# mini_board0.net
KiCad netlist of a schematic drawn in EAGLE
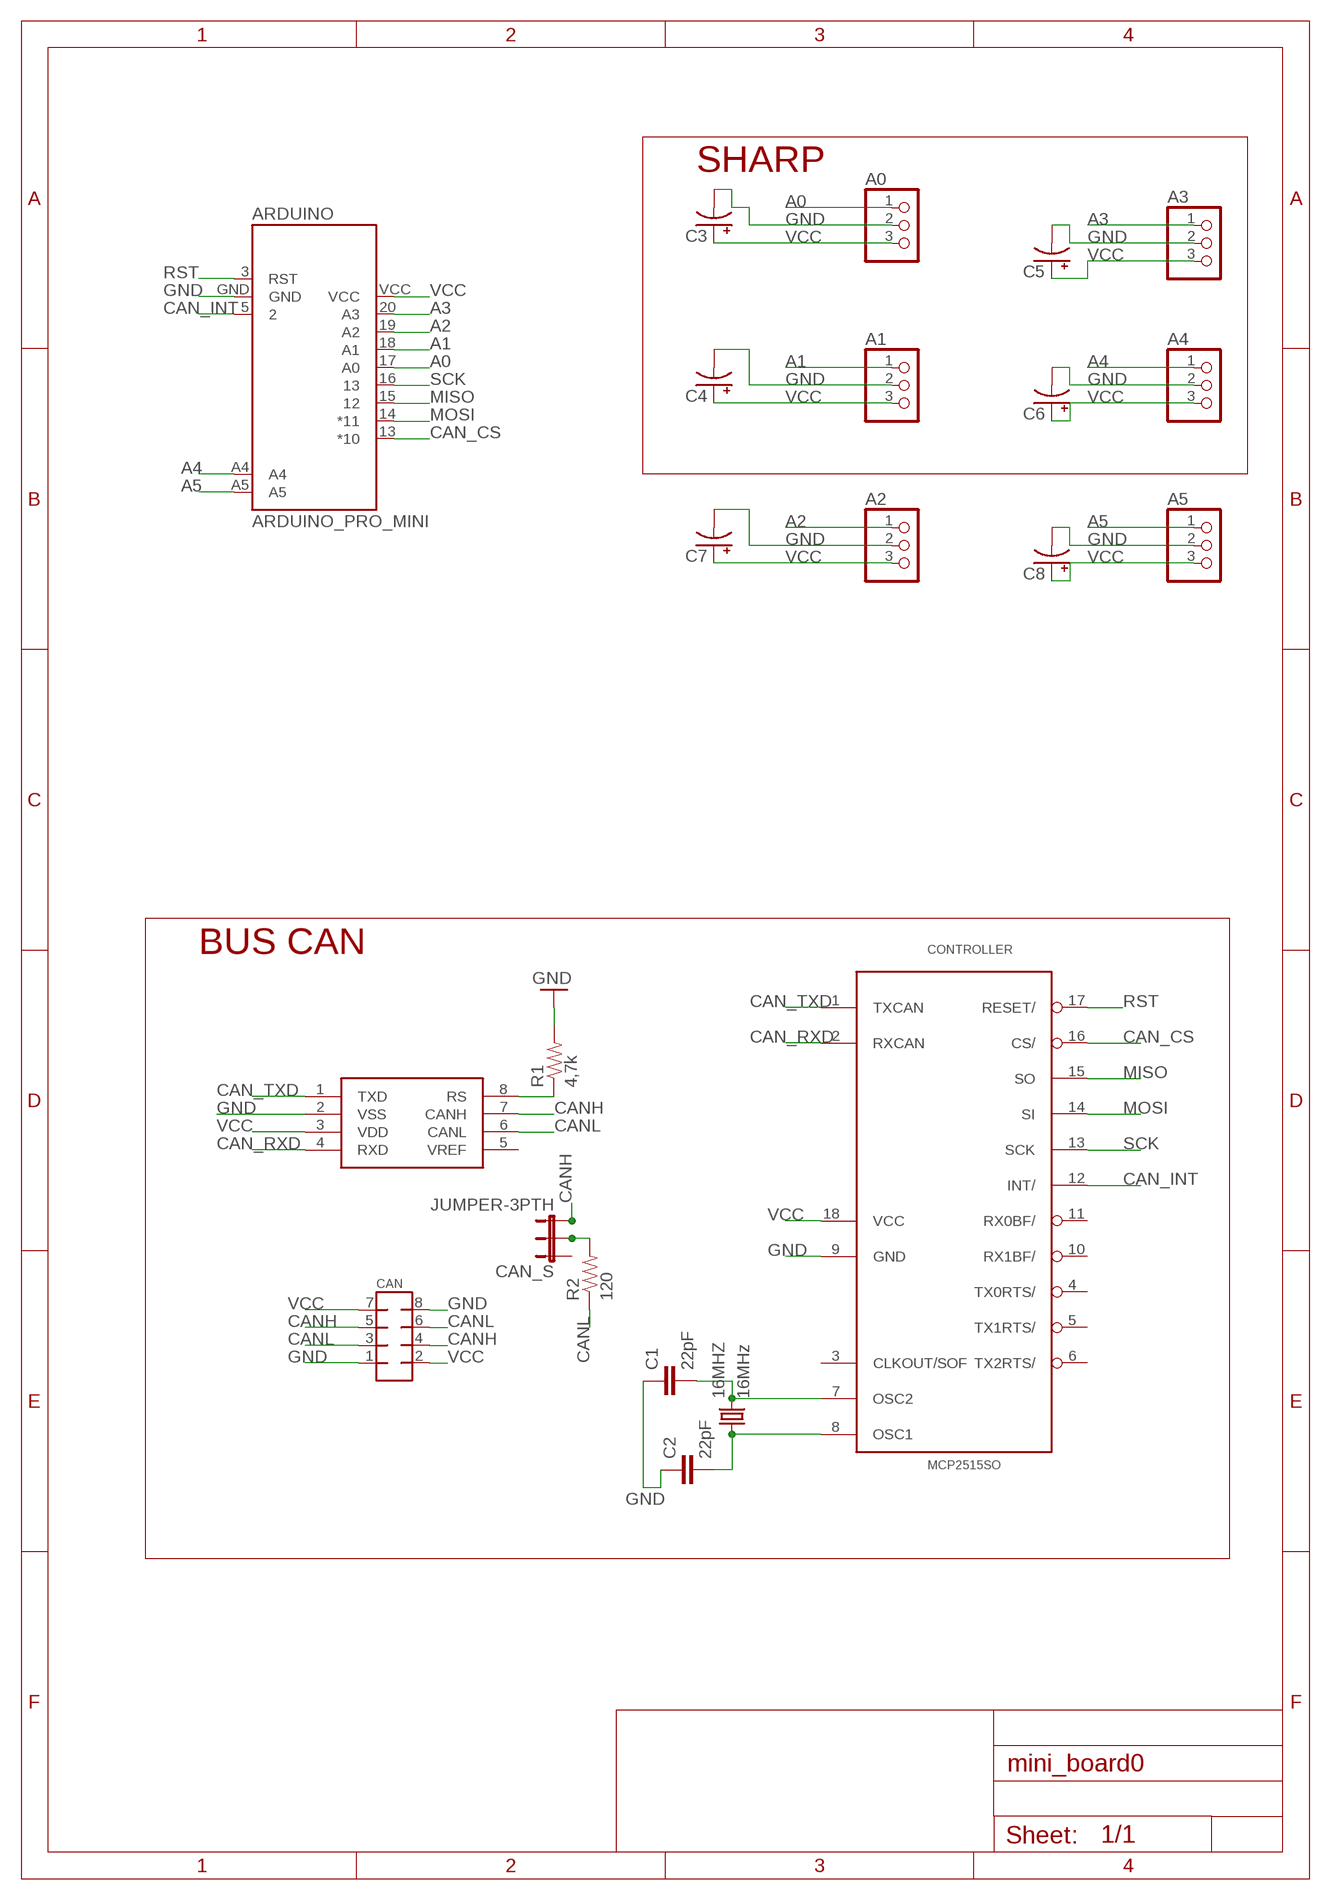
[diagram p0: schematic, sheet 1]

(export (version "E")
  (design (tool "Eeschema 10.0.6"))
  (components
    (comp (ref "16MHZ")
      (value "16MHz")
      (footprint "eagle-import:HC49_S")
      (libsource (lib "eagle-import") (part "CRYSTALHC49S"))
    )
    (comp (ref "A0")
      (value "PINHD-1X3/90")
      (footprint "eagle-import:1X03_90")
      (libsource (lib "eagle-import") (part "PINHD-1X3/90"))
    )
    (comp (ref "A1")
      (value "PINHD-1X3/90")
      (footprint "eagle-import:1X03_90")
      (libsource (lib "eagle-import") (part "PINHD-1X3/90"))
    )
    (comp (ref "A2")
      (value "PINHD-1X3/90")
      (footprint "eagle-import:1X03_90")
      (libsource (lib "eagle-import") (part "PINHD-1X3/90"))
    )
    (comp (ref "A3")
      (value "PINHD-1X3/90")
      (footprint "eagle-import:1X03_90")
      (libsource (lib "eagle-import") (part "PINHD-1X3/90"))
    )
    (comp (ref "A4")
      (value "PINHD-1X3/90")
      (footprint "eagle-import:1X03_90")
      (libsource (lib "eagle-import") (part "PINHD-1X3/90"))
    )
    (comp (ref "A5")
      (value "PINHD-1X3/90")
      (footprint "eagle-import:1X03_90")
      (libsource (lib "eagle-import") (part "PINHD-1X3/90"))
    )
    (comp (ref "ARDUINO")
      (value "ARDUINO_PRO_MINI")
      (footprint "eagle-import:ARDUINO_PRO_MINI")
      (libsource (lib "eagle-import") (part "ARDUINO_PRO_MINI"))
    )
    (comp (ref "C1")
      (value "22pF")
      (footprint "eagle-import:0805")
      (libsource (lib "eagle-import") (part "CAP0805"))
    )
    (comp (ref "C2")
      (value "22pF")
      (footprint "eagle-import:0805")
      (libsource (lib "eagle-import") (part "CAP0805"))
    )
    (comp (ref "C3")
      (value "CAP_POLPTH2")
      (footprint "eagle-import:CPOL-RADIAL-10UF-25V")
      (libsource (lib "eagle-import") (part "CAP_POLPTH2"))
    )
    (comp (ref "C4")
      (value "CAP_POLPTH2")
      (footprint "eagle-import:CPOL-RADIAL-10UF-25V")
      (libsource (lib "eagle-import") (part "CAP_POLPTH2"))
    )
    (comp (ref "C5")
      (value "CAP_POLPTH2")
      (footprint "eagle-import:CPOL-RADIAL-10UF-25V")
      (libsource (lib "eagle-import") (part "CAP_POLPTH2"))
    )
    (comp (ref "C6")
      (value "CAP_POLPTH2")
      (footprint "eagle-import:CPOL-RADIAL-10UF-25V")
      (libsource (lib "eagle-import") (part "CAP_POLPTH2"))
    )
    (comp (ref "C7")
      (value "CAP_POLPTH2")
      (footprint "eagle-import:CPOL-RADIAL-10UF-25V")
      (libsource (lib "eagle-import") (part "CAP_POLPTH2"))
    )
    (comp (ref "C8")
      (value "CAP_POLPTH2")
      (footprint "eagle-import:CPOL-RADIAL-10UF-25V")
      (libsource (lib "eagle-import") (part "CAP_POLPTH2"))
    )
    (comp (ref "CAN")
      (value "MMATCH-8-PTH")
      (footprint "eagle-import:AMP-215079-8")
      (libsource (lib "eagle-import") (part "MMATCH-8-PTH"))
    )
    (comp (ref "CAN_S")
      (value "JUMPER-3PTH")
      (footprint "eagle-import:1X03")
      (libsource (lib "eagle-import") (part "JUMPER-3PTH"))
    )
    (comp (ref "CONTROLLER")
      (value "MCP2515SO")
      (footprint "eagle-import:SO18L")
      (libsource (lib "eagle-import") (part "MCP2515SO"))
    )
    (comp (ref "R1")
      (value "4,7k")
      (footprint "eagle-import:0805")
      (libsource (lib "eagle-import") (part "RESISTOR0805-RES"))
    )
    (comp (ref "R2")
      (value "120")
      (footprint "eagle-import:0805")
      (libsource (lib "eagle-import") (part "RESISTOR0805-RES"))
    )
    (comp (ref "U1")
      (value "MCP2551")
      (footprint "eagle-import:SO08")
      (libsource (lib "eagle-import") (part "MCP2551"))
    )
  )
  (nets
    (net (code "1") (name "/A0") (class "Default")
      (node (ref "A0") (pin "1") (pinfunction "1_1") (pintype "passive"))
      (node (ref "ARDUINO") (pin "17") (pinfunction "A0_17") (pintype "bidirectional"))
    )
    (net (code "2") (name "/A1") (class "Default")
      (node (ref "A1") (pin "1") (pinfunction "1_1") (pintype "passive"))
      (node (ref "ARDUINO") (pin "18") (pinfunction "A1_18") (pintype "bidirectional"))
    )
    (net (code "3") (name "/A2") (class "Default")
      (node (ref "A2") (pin "1") (pinfunction "1_1") (pintype "passive"))
      (node (ref "ARDUINO") (pin "19") (pinfunction "A2_19") (pintype "bidirectional"))
    )
    (net (code "4") (name "/A3") (class "Default")
      (node (ref "A3") (pin "1") (pinfunction "1_1") (pintype "passive"))
      (node (ref "ARDUINO") (pin "20") (pinfunction "A3_20") (pintype "bidirectional"))
    )
    (net (code "5") (name "/A4") (class "Default")
      (node (ref "A4") (pin "1") (pinfunction "1_1") (pintype "passive"))
      (node (ref "ARDUINO") (pin "A4") (pinfunction "A4_A4") (pintype "bidirectional"))
    )
    (net (code "6") (name "/A5") (class "Default")
      (node (ref "A5") (pin "1") (pinfunction "1_1") (pintype "passive"))
      (node (ref "ARDUINO") (pin "A5") (pinfunction "A5_A5") (pintype "bidirectional"))
    )
    (net (code "7") (name "/CANH") (class "Default")
      (node (ref "CAN") (pin "4") (pinfunction "4_4") (pintype "bidirectional"))
      (node (ref "CAN") (pin "5") (pinfunction "5_5") (pintype "bidirectional"))
      (node (ref "CAN_S") (pin "3") (pinfunction "3_3") (pintype "passive"))
      (node (ref "U1") (pin "7") (pinfunction "CANH_7") (pintype "bidirectional"))
    )
    (net (code "8") (name "/CANL") (class "Default")
      (node (ref "CAN") (pin "3") (pinfunction "3_3") (pintype "bidirectional"))
      (node (ref "CAN") (pin "6") (pinfunction "6_6") (pintype "bidirectional"))
      (node (ref "R2") (pin "1") (pinfunction "1_1") (pintype "passive"))
      (node (ref "U1") (pin "6") (pinfunction "CANL_6") (pintype "bidirectional"))
    )
    (net (code "9") (name "/CAN_CS") (class "Default")
      (node (ref "ARDUINO") (pin "13") (pinfunction "*10_13") (pintype "bidirectional"))
      (node (ref "CONTROLLER") (pin "16") (pinfunction "CS/_16") (pintype "input"))
    )
    (net (code "10") (name "/CAN_INT") (class "Default")
      (node (ref "ARDUINO") (pin "5") (pinfunction "2_5") (pintype "bidirectional"))
      (node (ref "CONTROLLER") (pin "12") (pinfunction "INT/_12") (pintype "output"))
    )
    (net (code "11") (name "/CAN_RXD") (class "Default")
      (node (ref "CONTROLLER") (pin "2") (pinfunction "RXCAN_2") (pintype "input"))
      (node (ref "U1") (pin "4") (pinfunction "RXD_4") (pintype "bidirectional"))
    )
    (net (code "12") (name "/CAN_TXD") (class "Default")
      (node (ref "CONTROLLER") (pin "1") (pinfunction "TXCAN_1") (pintype "output"))
      (node (ref "U1") (pin "1") (pinfunction "TXD_1") (pintype "bidirectional"))
    )
    (net (code "13") (name "/MISO") (class "Default")
      (node (ref "ARDUINO") (pin "15") (pinfunction "12_15") (pintype "bidirectional"))
      (node (ref "CONTROLLER") (pin "15") (pinfunction "SO_15") (pintype "output"))
    )
    (net (code "14") (name "/MOSI") (class "Default")
      (node (ref "ARDUINO") (pin "14") (pinfunction "*11_14") (pintype "bidirectional"))
      (node (ref "CONTROLLER") (pin "14") (pinfunction "SI_14") (pintype "input"))
    )
    (net (code "15") (name "/RST") (class "Default")
      (node (ref "ARDUINO") (pin "3") (pinfunction "RST_3") (pintype "bidirectional"))
      (node (ref "CONTROLLER") (pin "17") (pinfunction "RESET/_17") (pintype "input"))
    )
    (net (code "16") (name "/SCK") (class "Default")
      (node (ref "ARDUINO") (pin "16") (pinfunction "13_16") (pintype "bidirectional"))
      (node (ref "CONTROLLER") (pin "13") (pinfunction "SCK_13") (pintype "input"))
    )
    (net (code "17") (name "/VCC") (class "Default")
      (node (ref "A0") (pin "3") (pinfunction "3_3") (pintype "passive"))
      (node (ref "A1") (pin "3") (pinfunction "3_3") (pintype "passive"))
      (node (ref "A2") (pin "3") (pinfunction "3_3") (pintype "passive"))
      (node (ref "A3") (pin "3") (pinfunction "3_3") (pintype "passive"))
      (node (ref "A4") (pin "3") (pinfunction "3_3") (pintype "passive"))
      (node (ref "A5") (pin "3") (pinfunction "3_3") (pintype "passive"))
      (node (ref "ARDUINO") (pin "VCC") (pinfunction "VCC_VCC") (pintype "bidirectional"))
      (node (ref "C3") (pin "1") (pinfunction "+_1") (pintype "passive"))
      (node (ref "C4") (pin "1") (pinfunction "+_1") (pintype "passive"))
      (node (ref "C5") (pin "1") (pinfunction "+_1") (pintype "passive"))
      (node (ref "C6") (pin "1") (pinfunction "+_1") (pintype "passive"))
      (node (ref "C7") (pin "1") (pinfunction "+_1") (pintype "passive"))
      (node (ref "C8") (pin "1") (pinfunction "+_1") (pintype "passive"))
      (node (ref "CAN") (pin "2") (pinfunction "2_2") (pintype "bidirectional"))
      (node (ref "CAN") (pin "7") (pinfunction "7_7") (pintype "bidirectional"))
      (node (ref "CONTROLLER") (pin "18") (pinfunction "VCC_18") (pintype "power_in"))
      (node (ref "U1") (pin "3") (pinfunction "VDD_3") (pintype "bidirectional"))
    )
    (net (code "18") (name "GND") (class "Default")
      (node (ref "A0") (pin "2") (pinfunction "2_2") (pintype "passive"))
      (node (ref "A1") (pin "2") (pinfunction "2_2") (pintype "passive"))
      (node (ref "A2") (pin "2") (pinfunction "2_2") (pintype "passive"))
      (node (ref "A3") (pin "2") (pinfunction "2_2") (pintype "passive"))
      (node (ref "A4") (pin "2") (pinfunction "2_2") (pintype "passive"))
      (node (ref "A5") (pin "2") (pinfunction "2_2") (pintype "passive"))
      (node (ref "ARDUINO") (pin "GND") (pinfunction "GND_GND") (pintype "bidirectional"))
      (node (ref "C1") (pin "1") (pinfunction "1_1") (pintype "passive"))
      (node (ref "C2") (pin "1") (pinfunction "1_1") (pintype "passive"))
      (node (ref "C3") (pin "2") (pinfunction "-_2") (pintype "passive"))
      (node (ref "C4") (pin "2") (pinfunction "-_2") (pintype "passive"))
      (node (ref "C5") (pin "2") (pinfunction "-_2") (pintype "passive"))
      (node (ref "C6") (pin "2") (pinfunction "-_2") (pintype "passive"))
      (node (ref "C7") (pin "2") (pinfunction "-_2") (pintype "passive"))
      (node (ref "C8") (pin "2") (pinfunction "-_2") (pintype "passive"))
      (node (ref "CAN") (pin "1") (pinfunction "1_1") (pintype "bidirectional"))
      (node (ref "CAN") (pin "8") (pinfunction "8_8") (pintype "bidirectional"))
      (node (ref "CONTROLLER") (pin "9") (pinfunction "GND_9") (pintype "power_in"))
      (node (ref "R1") (pin "2") (pinfunction "2_2") (pintype "passive"))
      (node (ref "U1") (pin "2") (pinfunction "VSS_2") (pintype "bidirectional"))
    )
    (net (code "19") (name "Net-(CAN_S-Pad2)") (class "Default")
      (node (ref "CAN_S") (pin "2") (pinfunction "2_2") (pintype "passive"))
      (node (ref "R2") (pin "2") (pinfunction "2_2") (pintype "passive"))
    )
    (net (code "20") (name "Net-(CONTROLLER-OSC1)") (class "Default")
      (node (ref "16MHZ") (pin "1") (pinfunction "1_1") (pintype "passive"))
      (node (ref "C2") (pin "2") (pinfunction "2_2") (pintype "passive"))
      (node (ref "CONTROLLER") (pin "8") (pinfunction "OSC1_8") (pintype "bidirectional"))
    )
    (net (code "21") (name "Net-(CONTROLLER-OSC2)") (class "Default")
      (node (ref "16MHZ") (pin "2") (pinfunction "2_2") (pintype "passive"))
      (node (ref "C1") (pin "2") (pinfunction "2_2") (pintype "passive"))
      (node (ref "CONTROLLER") (pin "7") (pinfunction "OSC2_7") (pintype "bidirectional"))
    )
    (net (code "22") (name "Net-(U1-RS)") (class "Default")
      (node (ref "R1") (pin "1") (pinfunction "1_1") (pintype "passive"))
      (node (ref "U1") (pin "8") (pinfunction "RS_8") (pintype "bidirectional"))
    )
    (net (code "23") (name "unconnected-(CAN_S-Pad1)") (class "Default")
      (node (ref "CAN_S") (pin "1") (pinfunction "1_1") (pintype "passive"))
    )
    (net (code "24") (name "unconnected-(CONTROLLER-CLKOUT{slash}SOF-Pad3)") (class "Default")
      (node (ref "CONTROLLER") (pin "3") (pinfunction "CLKOUT/SOF_3") (pintype "bidirectional"))
    )
    (net (code "25") (name "unconnected-(CONTROLLER-RX0BF{slash}-Pad11)") (class "Default")
      (node (ref "CONTROLLER") (pin "11") (pinfunction "RX0BF/_11") (pintype "bidirectional"))
    )
    (net (code "26") (name "unconnected-(CONTROLLER-RX1BF{slash}-Pad10)") (class "Default")
      (node (ref "CONTROLLER") (pin "10") (pinfunction "RX1BF/_10") (pintype "bidirectional"))
    )
    (net (code "27") (name "unconnected-(CONTROLLER-TX0RTS{slash}-Pad4)") (class "Default")
      (node (ref "CONTROLLER") (pin "4") (pinfunction "TX0RTS/_4") (pintype "bidirectional"))
    )
    (net (code "28") (name "unconnected-(CONTROLLER-TX1RTS{slash}-Pad5)") (class "Default")
      (node (ref "CONTROLLER") (pin "5") (pinfunction "TX1RTS/_5") (pintype "bidirectional"))
    )
    (net (code "29") (name "unconnected-(CONTROLLER-TX2RTS{slash}-Pad6)") (class "Default")
      (node (ref "CONTROLLER") (pin "6") (pinfunction "TX2RTS/_6") (pintype "bidirectional"))
    )
    (net (code "30") (name "unconnected-(U1-VREF-Pad5)") (class "Default")
      (node (ref "U1") (pin "5") (pinfunction "VREF_5") (pintype "bidirectional"))
    )
  )
)
